# EEGAmp_SMT.net
KiCad netlist of a schematic drawn in EAGLE
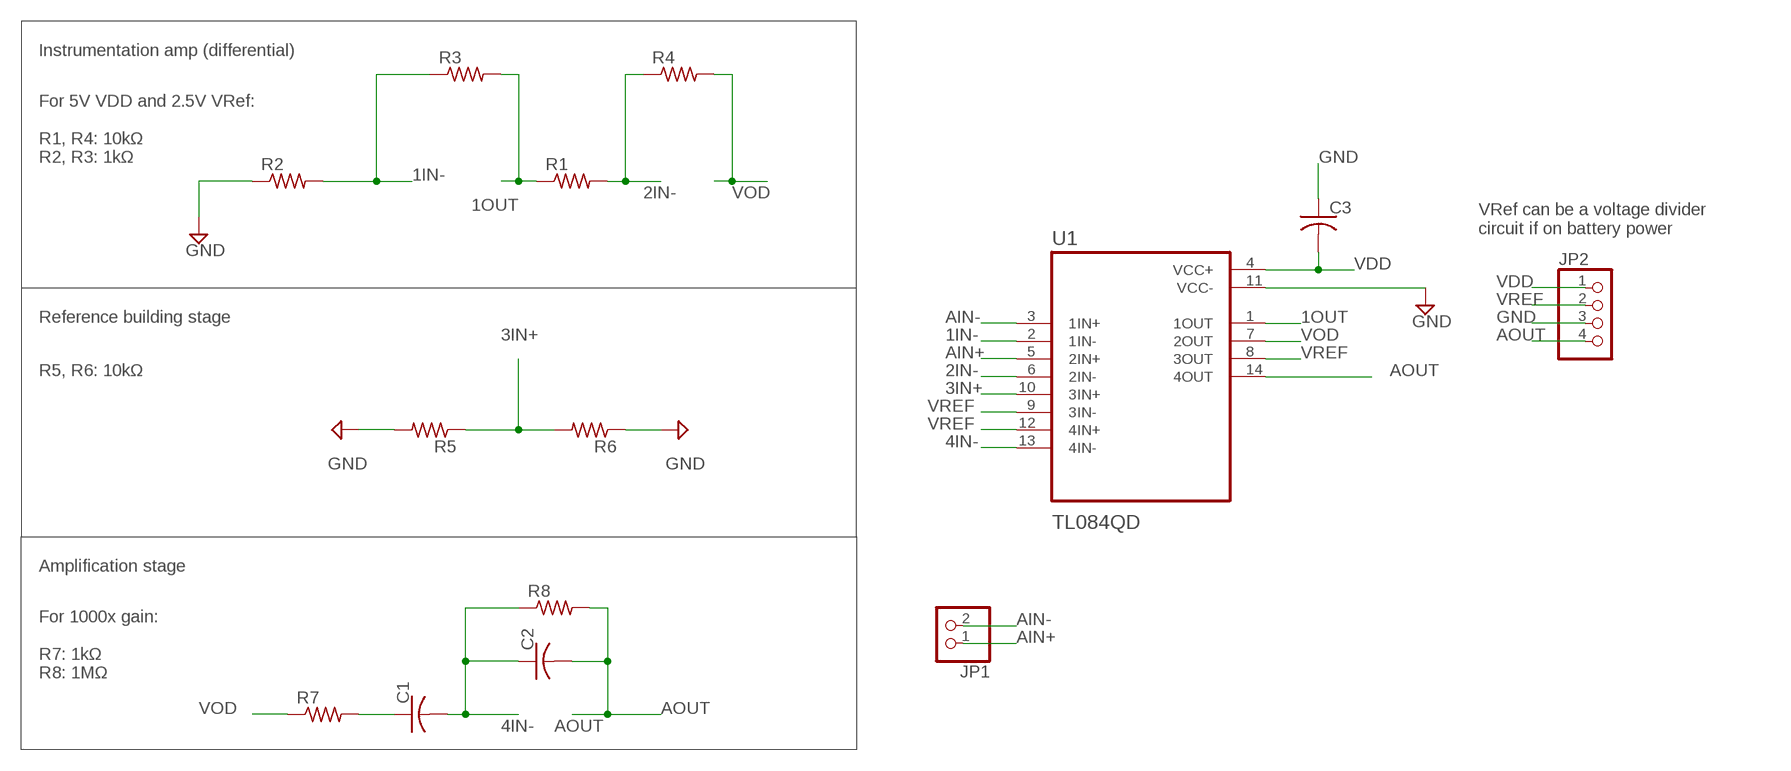
[diagram p0: schematic, sheet 1]

(export (version "E")
  (design (tool "Eeschema 10.0.6"))
  (components
    (comp (ref "C1")
      (value "C-USC0402")
      (footprint "eagle-import:C0402")
      (libsource (lib "eagle-import") (part "C-USC0402"))
    )
    (comp (ref "C2")
      (value "C-USC0402")
      (footprint "eagle-import:C0402")
      (libsource (lib "eagle-import") (part "C-USC0402"))
    )
    (comp (ref "C3")
      (value "C-USC0402")
      (footprint "eagle-import:C0402")
      (libsource (lib "eagle-import") (part "C-USC0402"))
    )
    (comp (ref "JP1")
      (value "PINHD-1X2")
      (footprint "eagle-import:1X02")
      (libsource (lib "eagle-import") (part "PINHD-1X2"))
    )
    (comp (ref "JP2")
      (value "PINHD-1X4")
      (footprint "eagle-import:1X04")
      (libsource (lib "eagle-import") (part "PINHD-1X4"))
    )
    (comp (ref "R1")
      (value "R-US_R0402")
      (footprint "eagle-import:R0402")
      (libsource (lib "eagle-import") (part "R-US_R0402"))
    )
    (comp (ref "R2")
      (value "R-US_R0402")
      (footprint "eagle-import:R0402")
      (libsource (lib "eagle-import") (part "R-US_R0402"))
    )
    (comp (ref "R3")
      (value "R-US_R0402")
      (footprint "eagle-import:R0402")
      (libsource (lib "eagle-import") (part "R-US_R0402"))
    )
    (comp (ref "R4")
      (value "R-US_R0402")
      (footprint "eagle-import:R0402")
      (libsource (lib "eagle-import") (part "R-US_R0402"))
    )
    (comp (ref "R5")
      (value "R-US_R0402")
      (footprint "eagle-import:R0402")
      (libsource (lib "eagle-import") (part "R-US_R0402"))
    )
    (comp (ref "R6")
      (value "R-US_R0402")
      (footprint "eagle-import:R0402")
      (libsource (lib "eagle-import") (part "R-US_R0402"))
    )
    (comp (ref "R7")
      (value "R-US_R0402")
      (footprint "eagle-import:R0402")
      (libsource (lib "eagle-import") (part "R-US_R0402"))
    )
    (comp (ref "R8")
      (value "R-US_R0402")
      (footprint "eagle-import:R0402")
      (libsource (lib "eagle-import") (part "R-US_R0402"))
    )
    (comp (ref "U1")
      (value "TL084QD")
      (footprint "eagle-import:SOIC127P600X175-14N")
      (fields (field (name "MF") "Texas Instruments"))
      (libsource (lib "eagle-import") (part "TL084QD"))
    )
  )
  (nets
    (net (code "1") (name "/1IN-") (class "Default")
      (node (ref "R2") (pin "2") (pinfunction "2_2") (pintype "passive"))
      (node (ref "R3") (pin "1") (pinfunction "1_1") (pintype "passive"))
      (node (ref "U1") (pin "2") (pinfunction "1IN-_2") (pintype "input"))
    )
    (net (code "2") (name "/1OUT") (class "Default")
      (node (ref "R1") (pin "1") (pinfunction "1_1") (pintype "passive"))
      (node (ref "R3") (pin "2") (pinfunction "2_2") (pintype "passive"))
      (node (ref "U1") (pin "1") (pinfunction "1OUT_1") (pintype "output"))
    )
    (net (code "3") (name "/2IN-") (class "Default")
      (node (ref "R1") (pin "2") (pinfunction "2_2") (pintype "passive"))
      (node (ref "R4") (pin "1") (pinfunction "1_1") (pintype "passive"))
      (node (ref "U1") (pin "6") (pinfunction "2IN-_6") (pintype "input"))
    )
    (net (code "4") (name "/3IN+") (class "Default")
      (node (ref "R5") (pin "1") (pinfunction "1_1") (pintype "passive"))
      (node (ref "R6") (pin "2") (pinfunction "2_2") (pintype "passive"))
      (node (ref "U1") (pin "10") (pinfunction "3IN+_10") (pintype "input"))
    )
    (net (code "5") (name "/4IN-") (class "Default")
      (node (ref "C1") (pin "2") (pinfunction "2_2") (pintype "passive"))
      (node (ref "C2") (pin "1") (pinfunction "1_1") (pintype "passive"))
      (node (ref "R8") (pin "1") (pinfunction "1_1") (pintype "passive"))
      (node (ref "U1") (pin "13") (pinfunction "4IN-_13") (pintype "input"))
    )
    (net (code "6") (name "/AIN+") (class "Default")
      (node (ref "JP1") (pin "1") (pinfunction "1_1") (pintype "passive"))
      (node (ref "U1") (pin "5") (pinfunction "2IN+_5") (pintype "input"))
    )
    (net (code "7") (name "/AIN-") (class "Default")
      (node (ref "JP1") (pin "2") (pinfunction "2_2") (pintype "passive"))
      (node (ref "U1") (pin "3") (pinfunction "1IN+_3") (pintype "input"))
    )
    (net (code "8") (name "/AOUT") (class "Default")
      (node (ref "C2") (pin "2") (pinfunction "2_2") (pintype "passive"))
      (node (ref "JP2") (pin "4") (pinfunction "4_4") (pintype "passive"))
      (node (ref "R8") (pin "2") (pinfunction "2_2") (pintype "passive"))
      (node (ref "U1") (pin "14") (pinfunction "4OUT_14") (pintype "output"))
    )
    (net (code "9") (name "/VDD") (class "Default")
      (node (ref "C3") (pin "2") (pinfunction "2_2") (pintype "passive"))
      (node (ref "JP2") (pin "1") (pinfunction "1_1") (pintype "passive"))
      (node (ref "U1") (pin "4") (pinfunction "VCC+_4") (pintype "power_in"))
    )
    (net (code "10") (name "/VOD") (class "Default")
      (node (ref "R4") (pin "2") (pinfunction "2_2") (pintype "passive"))
      (node (ref "R7") (pin "1") (pinfunction "1_1") (pintype "passive"))
      (node (ref "U1") (pin "7") (pinfunction "2OUT_7") (pintype "output"))
    )
    (net (code "11") (name "/VREF") (class "Default")
      (node (ref "JP2") (pin "2") (pinfunction "2_2") (pintype "passive"))
      (node (ref "U1") (pin "12") (pinfunction "4IN+_12") (pintype "input"))
      (node (ref "U1") (pin "8") (pinfunction "3OUT_8") (pintype "output"))
      (node (ref "U1") (pin "9") (pinfunction "3IN-_9") (pintype "input"))
    )
    (net (code "12") (name "GND") (class "Default")
      (node (ref "C3") (pin "1") (pinfunction "1_1") (pintype "passive"))
      (node (ref "JP2") (pin "3") (pinfunction "3_3") (pintype "passive"))
      (node (ref "R2") (pin "1") (pinfunction "1_1") (pintype "passive"))
      (node (ref "R5") (pin "2") (pinfunction "2_2") (pintype "passive"))
      (node (ref "R6") (pin "1") (pinfunction "1_1") (pintype "passive"))
      (node (ref "U1") (pin "11") (pinfunction "VCC-_11") (pintype "power_in"))
    )
    (net (code "13") (name "Net-(C1-Pad1)") (class "Default")
      (node (ref "C1") (pin "1") (pinfunction "1_1") (pintype "passive"))
      (node (ref "R7") (pin "2") (pinfunction "2_2") (pintype "passive"))
    )
  )
)
